# AC_Input_Rectifier.net
KiCad netlist of a schematic drawn in Altium Designer
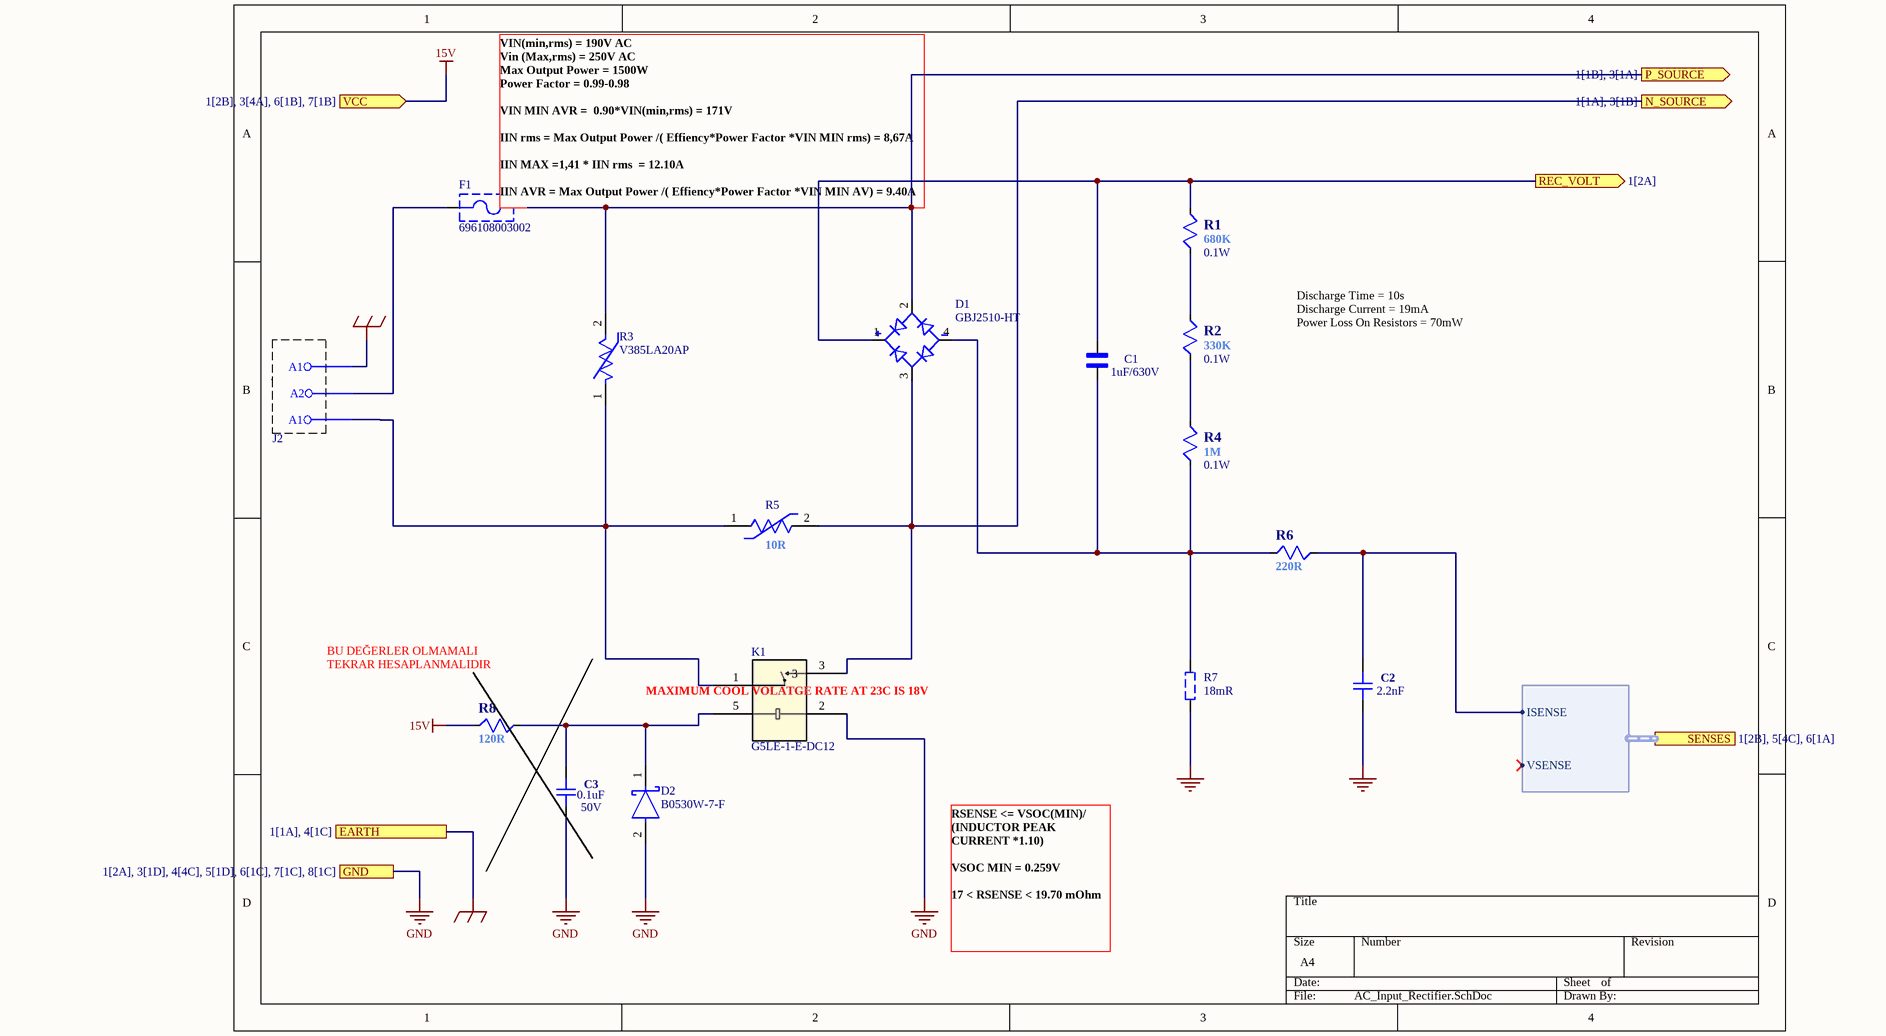
[diagram p0: AC_Input_Rectifier.SchDoc]

(export (version "E")
  (design (tool "Eeschema 10.0.6"))
  (components
    (comp (ref "C1")
      (value "1uF/630V")
      (footprint "CAPRR3750W100L4150T1800H3250")
      (fields (field (name "MF") "TDK Electronics") (field (name "MP") "B32026A3105M000"))
      (libsource (lib "Görev Yükü's Libary") (part "B32026A3105M000"))
    )
    (comp (ref "C2")
      (value "2.2nF")
      (footprint "CAPC1608N")
      (description "MLCC (1608) 0603 2.2nF 50VDC ±10% X7R")
      (fields (field (name "Comment") "CL10B222KB8NNNC"))
      (libsource (lib "WG_MainBoard_NV2") (part "CAP_0805"))
    )
    (comp (ref "C3")
      (value "0.1uF")
      (footprint "CAPC1608N")
      (description "MLCC (1608) 0603 100nF 50VDC ±10% X7R")
      (fields (field (name "RATING") "50V") (field (name "Comment") "CL10B104KB8NNNC"))
      (libsource (lib "WG_MainBoard_NV2") (part "CAP_0805"))
    )
    (comp (ref "D1")
      (value "GBJ2510-HT")
      (footprint "DIOB_GBJ2510-F")
      (description "DIODE BRIDGE 25A 1000V")
      (fields (field (name "MF") "Micro Commercial") (field (name "MP") "GBJ3510-BP"))
      (libsource (lib "Görev Yükü's Libary") (part "GBJ2510-HT"))
    )
    (comp (ref "D2")
      (value "B0530W-7-F")
      (footprint "FP-SOD123-MFG")
      (description "DIODE SCHOTTKY 30V 500MA SOD123")
      (fields
        (field (name "MANUFACTURER") "Diodes Inc.")
        (field (name "OCTOPART") "https://octopart.com/b0530w-7-f-diodes+inc.-325721")
      )
      (libsource (lib "Altium Content Vault") (part "1d6ec82d83fb6aee721767c19dac4b9"))
    )
    (comp (ref "F1")
      (value "696108003002")
      (footprint "696108003002")
      (description "FUSE HOLDER 5x20 TK79 PLASTIC")
      (libsource (lib "Altium Content Vault") (part "Fuse Holder"))
    )
    (comp (ref "J2")
      (value "DG25S-B-03P-13-00AH")
      (footprint "DG28C-B-03P")
      (description "TERM.BLK.7.62MM 3P BARRIER TERMINAL BLACK")
      (libsource (lib "Görev Yükü's Libary") (part "DG25S-B-03P-13-00AH"))
    )
    (comp (ref "K1")
      (value "G5LE-1-E-DC12")
      (footprint "G5LE-1-E-DC12")
      (description "RELAY POWER 16A 12V 1FormC 5PIN")
      (fields (field (name "COPYRIGHT") "Copyright (C) 2025 Ultra Librarian. All rights reserved."))
      (libsource (lib "Görev Yükü's Libary") (part "G5LE-1-E-DC12"))
    )
    (comp (ref "R1")
      (value "680K")
      (footprint "PCB_EZ_BuckPowerDriver V2.0:RESC1608N")
      (description "RES.(1608) 0603 680K Ohms 1% 1/10W 100PPM,")
      (fields (field (name "POWER DISSIPATION") "0.1W") (field (name "Comment") "CRT03F7E6803"))
      (libsource (lib "WG_MainBoard_NV1") (part "RES"))
    )
    (comp (ref "R2")
      (value "330K")
      (footprint "PCB_EZ_BuckPowerDriver V2.0:RESC1608N")
      (description "RES.(1608) 0603 330K Ohms 5% 1/10W 100PPM SMT,")
      (fields (field (name "POWER DISSIPATION") "0.1W") (field (name "Comment") "RC0603JR-07330KL"))
      (libsource (lib "WG_MainBoard_NV1") (part "RES"))
    )
    (comp (ref "R3")
      (value "V385LA20AP")
      (footprint "FP-B72214S0301K101-0")
      (description "VARISTOR 470V 4.5KA DISC 14MM")
      (fields (field (name "TOLERANCE") "10%"))
      (libsource (lib "Altium Content Vault") (part "78a88060d5b7b043d6e48adc4284376"))
    )
    (comp (ref "R4")
      (value "1M")
      (footprint "PCB_EZ_BuckPowerDriver V2.0:RESC1608N")
      (description "RES.(1608) 0603 1M Ohms 5% 1/10W 200PPM,")
      (fields (field (name "POWER DISSIPATION") "0.1W") (field (name "Comment") "RI0603L105JT"))
      (libsource (lib "WG_MainBoard_NV1") (part "RES"))
    )
    (comp (ref "R5")
      (value "PPL19100HA1B7CKB")
      (footprint "FP-PGTL_P5_D7_4_T4_H13_4-MFG")
      (description "THERMISTOR PTC 10R 270VAC")
      (fields (field (name "RESISTANCE") "10R"))
      (libsource (lib "Altium Content Vault") (part "1c6d77a0208143737455a0c7eb396be"))
    )
    (comp (ref "R6")
      (value "220R")
      (footprint "PCB_EZ_BuckPowerDriver V2.0:RESC1608N")
      (description "RES.(1608) 0603 220 Ohms 1% 1/10W-S 100PPM")
      (fields (field (name "Comment") "0603SAF2200T5E"))
      (libsource (lib "WG_MainBoard_NV1") (part "RES"))
    )
    (comp (ref "R7")
      (value "18mR")
      (footprint "CSS2H-2512")
      (description "18 mOhms ±1% 2W Chip Resistor 2512 (6332 Metric) Automotive AEC-Q200, Current Sense Metal Film")
      (fields
        (field (name "MANUFACTURER") "YAGEO")
        (field (name "MANUFACTURER PART NUMBER") "PE2512FKE7W0R018L")
      )
      (libsource (lib "Phil-lab") (part "CSS2H-2512"))
    )
    (comp (ref "R8")
      (value "120R")
      (footprint "PCB_EZ_BuckPowerDriver V2.0:RESC1608N")
      (description "RES.(1608) 0603 120 Ohms 5% 1/10W-S 100PPM")
      (fields (field (name "Comment") "CRT03J7E1200"))
      (libsource (lib "WG_MainBoard_NV1") (part "RES"))
    )
  )
  (nets
    (net (code "2") (name "/N_SOURCE") (class "Default")
      (node (ref "D1") (pin "3") (pinfunction "AC2_3") (pintype "passive"))
      (node (ref "K1") (pin "3") (pinfunction "3_3") (pintype "passive"))
      (node (ref "R5") (pin "2") (pinfunction "2_2") (pintype "passive"))
    )
    (net (code "3") (name "/P_SOURCE") (class "Default")
      (node (ref "D1") (pin "2") (pinfunction "AC1_2") (pintype "passive"))
      (node (ref "F1") (pin "2") (pinfunction "2_2") (pintype "passive"))
      (node (ref "R3") (pin "2") (pinfunction "2_2") (pintype "passive"))
    )
    (net (code "4") (name "/REC_VOLT") (class "Default")
      (node (ref "C1") (pin "2") (pinfunction "2_2") (pintype "passive"))
      (node (ref "D1") (pin "1") (pinfunction "POS_1") (pintype "passive"))
      (node (ref "R1") (pin "1") (pinfunction "1_1") (pintype "passive"))
    )
    (net (code "6") (name "15V") (class "Default")
      (node (ref "R8") (pin "1") (pinfunction "1_1") (pintype "passive"))
    )
    (net (code "7") (name "EARTH") (class "Default")
      (node (ref "J2") (pin "3") (pinfunction "A1_3") (pintype "passive"))
    )
    (net (code "8") (name "GND") (class "Default")
      (node (ref "C2") (pin "1") (pinfunction "1_1") (pintype "passive"))
      (node (ref "C3") (pin "1") (pinfunction "1_1") (pintype "passive"))
      (node (ref "D2") (pin "2") (pinfunction "A_2") (pintype "passive"))
      (node (ref "K1") (pin "2") (pinfunction "2_2") (pintype "passive"))
      (node (ref "R7") (pin "1") (pinfunction "1_1") (pintype "passive"))
    )
    (net (code "9") (name "Net-(C2-Pad2)") (class "Default")
      (node (ref "C2") (pin "2") (pinfunction "2_2") (pintype "passive"))
      (node (ref "R6") (pin "2") (pinfunction "2_2") (pintype "passive"))
    )
    (net (code "10") (name "Net-(D1-NEG)") (class "Default")
      (node (ref "C1") (pin "1") (pinfunction "1_1") (pintype "passive"))
      (node (ref "D1") (pin "4") (pinfunction "NEG_4") (pintype "passive"))
      (node (ref "R4") (pin "2") (pinfunction "2_2") (pintype "passive"))
      (node (ref "R6") (pin "1") (pinfunction "1_1") (pintype "passive"))
      (node (ref "R7") (pin "2") (pinfunction "2_2") (pintype "passive"))
    )
    (net (code "11") (name "Net-(D2-C)") (class "Default")
      (node (ref "C3") (pin "2") (pinfunction "2_2") (pintype "passive"))
      (node (ref "D2") (pin "1") (pinfunction "C_1") (pintype "passive"))
      (node (ref "K1") (pin "5") (pinfunction "5_5") (pintype "passive"))
      (node (ref "R8") (pin "2") (pinfunction "2_2") (pintype "passive"))
    )
    (net (code "12") (name "Net-(J2-A1-Pad1)") (class "Default")
      (node (ref "J2") (pin "1") (pinfunction "A1_1") (pintype "passive"))
      (node (ref "K1") (pin "1") (pinfunction "1_1") (pintype "passive"))
      (node (ref "R3") (pin "1") (pinfunction "1_1") (pintype "passive"))
      (node (ref "R5") (pin "1") (pinfunction "1_1") (pintype "passive"))
    )
    (net (code "13") (name "Net-(J2-A2)") (class "Default")
      (node (ref "F1") (pin "1") (pinfunction "1_1") (pintype "passive"))
      (node (ref "J2") (pin "2") (pinfunction "A2_2") (pintype "passive"))
    )
    (net (code "14") (name "Net-(R1-Pad2)") (class "Default")
      (node (ref "R1") (pin "2") (pinfunction "2_2") (pintype "passive"))
      (node (ref "R2") (pin "1") (pinfunction "1_1") (pintype "passive"))
    )
    (net (code "15") (name "Net-(R2-Pad2)") (class "Default")
      (node (ref "R2") (pin "2") (pinfunction "2_2") (pintype "passive"))
      (node (ref "R4") (pin "1") (pinfunction "1_1") (pintype "passive"))
    )
  )
)
